# M602X.net
KiCad netlist of a schematic drawn in EAGLE
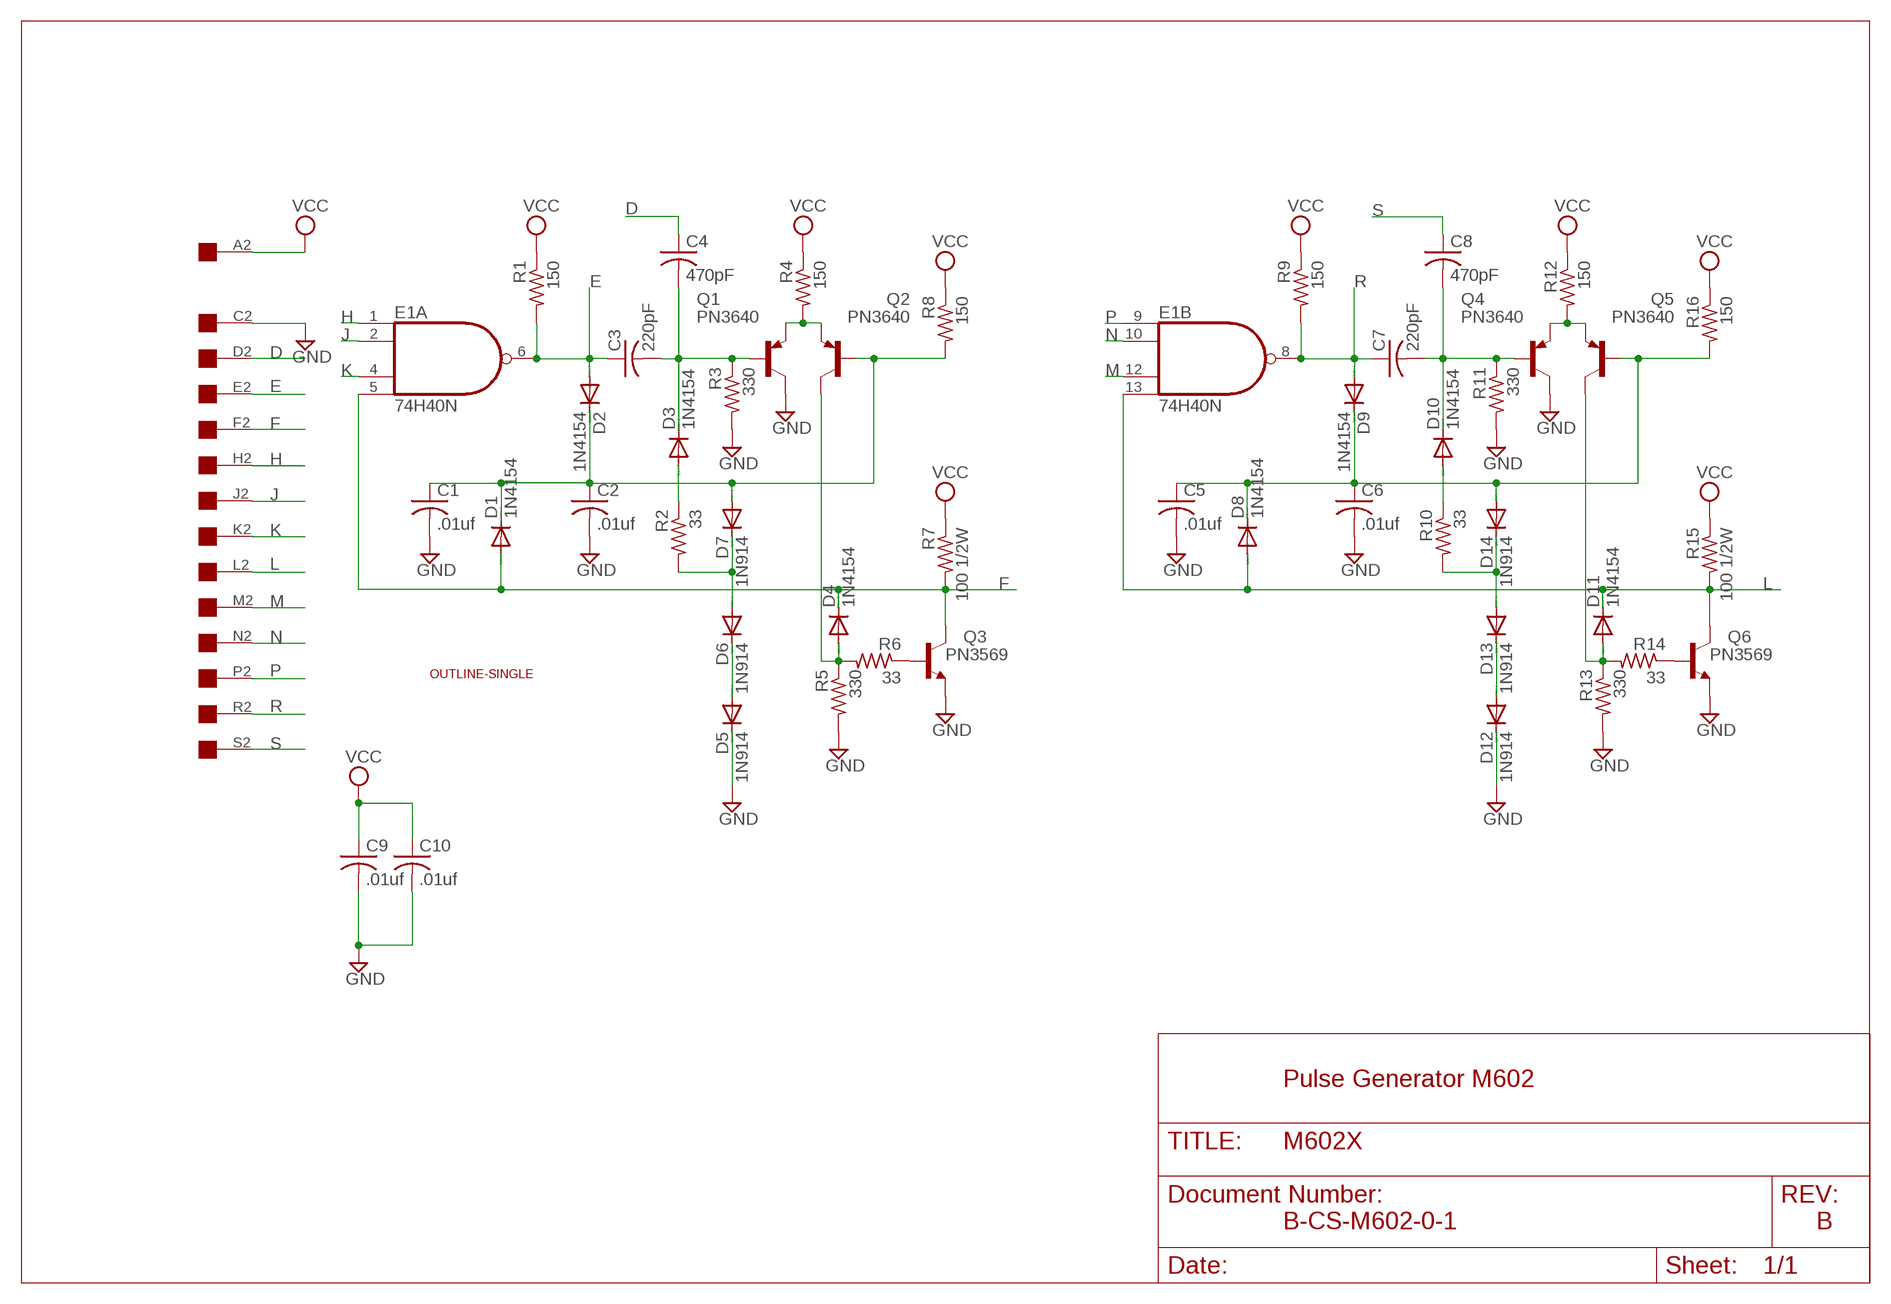
[diagram p0: schematic, sheet 1]

(export (version "E")
  (design (tool "Eeschema 10.0.6"))
  (components
    (comp (ref "C1")
      (value ".01uf")
      (footprint "eagle-import:C075-032X103")
      (libsource (lib "eagle-import") (part "C-US075-032X103"))
    )
    (comp (ref "C2")
      (value ".01uf")
      (footprint "eagle-import:C075-032X103")
      (libsource (lib "eagle-import") (part "C-US075-032X103"))
    )
    (comp (ref "C3")
      (value "220pF")
      (footprint "eagle-import:C150-054X183")
      (libsource (lib "eagle-import") (part "C-US150-054X183"))
    )
    (comp (ref "C4")
      (value "470pF")
      (footprint "eagle-import:C150-054X183")
      (libsource (lib "eagle-import") (part "C-US150-054X183"))
    )
    (comp (ref "C5")
      (value ".01uf")
      (footprint "eagle-import:C075-032X103")
      (libsource (lib "eagle-import") (part "C-US075-032X103"))
    )
    (comp (ref "C6")
      (value ".01uf")
      (footprint "eagle-import:C075-032X103")
      (libsource (lib "eagle-import") (part "C-US075-032X103"))
    )
    (comp (ref "C7")
      (value "220pF")
      (footprint "eagle-import:C150-054X183")
      (libsource (lib "eagle-import") (part "C-US150-054X183"))
    )
    (comp (ref "C8")
      (value "470pF")
      (footprint "eagle-import:C150-054X183")
      (libsource (lib "eagle-import") (part "C-US150-054X183"))
    )
    (comp (ref "C9")
      (value ".01uf")
      (footprint "eagle-import:C050-025X075")
      (libsource (lib "eagle-import") (part "C-US050-025X075"))
    )
    (comp (ref "C10")
      (value ".01uf")
      (footprint "eagle-import:C075-032X103")
      (libsource (lib "eagle-import") (part "C-US075-032X103"))
    )
    (comp (ref "D1")
      (value "1N4154")
      (footprint "eagle-import:DO41-10")
      (libsource (lib "eagle-import") (part "1N4004"))
    )
    (comp (ref "D2")
      (value "1N4154")
      (footprint "eagle-import:DO41-10")
      (libsource (lib "eagle-import") (part "1N4004"))
    )
    (comp (ref "D3")
      (value "1N4154")
      (footprint "eagle-import:DO41-10")
      (libsource (lib "eagle-import") (part "1N4004"))
    )
    (comp (ref "D4")
      (value "1N4154")
      (footprint "eagle-import:DO41-10")
      (libsource (lib "eagle-import") (part "1N4004"))
    )
    (comp (ref "D5")
      (value "1N914")
      (footprint "eagle-import:DO41-10")
      (libsource (lib "eagle-import") (part "1N4004"))
    )
    (comp (ref "D6")
      (value "1N914")
      (footprint "eagle-import:DO41-10")
      (libsource (lib "eagle-import") (part "1N4004"))
    )
    (comp (ref "D7")
      (value "1N914")
      (footprint "eagle-import:DO41-10")
      (libsource (lib "eagle-import") (part "1N4004"))
    )
    (comp (ref "D8")
      (value "1N4154")
      (footprint "eagle-import:DO41-10")
      (libsource (lib "eagle-import") (part "1N4004"))
    )
    (comp (ref "D9")
      (value "1N4154")
      (footprint "eagle-import:DO41-10")
      (libsource (lib "eagle-import") (part "1N4004"))
    )
    (comp (ref "D10")
      (value "1N4154")
      (footprint "eagle-import:DO41-10")
      (libsource (lib "eagle-import") (part "1N4004"))
    )
    (comp (ref "D11")
      (value "1N4154")
      (footprint "eagle-import:DO41-10")
      (libsource (lib "eagle-import") (part "1N4004"))
    )
    (comp (ref "D12")
      (value "1N914")
      (footprint "eagle-import:DO41-10")
      (libsource (lib "eagle-import") (part "1N4004"))
    )
    (comp (ref "D13")
      (value "1N914")
      (footprint "eagle-import:DO41-10")
      (libsource (lib "eagle-import") (part "1N4004"))
    )
    (comp (ref "D14")
      (value "1N914")
      (footprint "eagle-import:DO41-10")
      (libsource (lib "eagle-import") (part "1N4004"))
    )
    (comp (ref "E1")
      (value "74H40N")
      (footprint "eagle-import:DIL14")
      (libsource (lib "eagle-import") (part "7420NLS"))
    )
    (comp (ref "Q1")
      (value "PN3640")
      (footprint "eagle-import:TO39")
      (libsource (lib "eagle-import") (part "2N5415"))
    )
    (comp (ref "Q2")
      (value "PN3640")
      (footprint "eagle-import:TO39")
      (libsource (lib "eagle-import") (part "2N5415"))
    )
    (comp (ref "Q3")
      (value "PN3569")
      (footprint "eagle-import:TO39")
      (libsource (lib "eagle-import") (part "2N1711"))
    )
    (comp (ref "Q4")
      (value "PN3640")
      (footprint "eagle-import:TO39")
      (libsource (lib "eagle-import") (part "2N5415"))
    )
    (comp (ref "Q5")
      (value "PN3640")
      (footprint "eagle-import:TO39")
      (libsource (lib "eagle-import") (part "2N5415"))
    )
    (comp (ref "Q6")
      (value "PN3569")
      (footprint "eagle-import:TO39")
      (libsource (lib "eagle-import") (part "2N1711"))
    )
    (comp (ref "R1")
      (value "150")
      (footprint "eagle-import:0207_10")
      (libsource (lib "eagle-import") (part "R-US_0207/10"))
    )
    (comp (ref "R2")
      (value "33")
      (footprint "eagle-import:0207_10")
      (libsource (lib "eagle-import") (part "R-US_0207/10"))
    )
    (comp (ref "R3")
      (value "330")
      (footprint "eagle-import:0207_10")
      (libsource (lib "eagle-import") (part "R-US_0207/10"))
    )
    (comp (ref "R4")
      (value "150")
      (footprint "eagle-import:0207_10")
      (libsource (lib "eagle-import") (part "R-US_0207/10"))
    )
    (comp (ref "R5")
      (value "330")
      (footprint "eagle-import:0207_10")
      (libsource (lib "eagle-import") (part "R-US_0207/10"))
    )
    (comp (ref "R6")
      (value "33")
      (footprint "eagle-import:0207_10")
      (libsource (lib "eagle-import") (part "R-US_0207/10"))
    )
    (comp (ref "R7")
      (value "100 1/2W")
      (footprint "eagle-import:0309_12")
      (libsource (lib "eagle-import") (part "R-US_0309/12"))
    )
    (comp (ref "R8")
      (value "150")
      (footprint "eagle-import:0207_10")
      (libsource (lib "eagle-import") (part "R-US_0207/10"))
    )
    (comp (ref "R9")
      (value "150")
      (footprint "eagle-import:0207_10")
      (libsource (lib "eagle-import") (part "R-US_0207/10"))
    )
    (comp (ref "R10")
      (value "33")
      (footprint "eagle-import:0207_10")
      (libsource (lib "eagle-import") (part "R-US_0207/10"))
    )
    (comp (ref "R11")
      (value "330")
      (footprint "eagle-import:0207_10")
      (libsource (lib "eagle-import") (part "R-US_0207/10"))
    )
    (comp (ref "R12")
      (value "150")
      (footprint "eagle-import:0207_10")
      (libsource (lib "eagle-import") (part "R-US_0207/10"))
    )
    (comp (ref "R13")
      (value "330")
      (footprint "eagle-import:0207_10")
      (libsource (lib "eagle-import") (part "R-US_0207/10"))
    )
    (comp (ref "R14")
      (value "33")
      (footprint "eagle-import:0207_10")
      (libsource (lib "eagle-import") (part "R-US_0207/10"))
    )
    (comp (ref "R15")
      (value "100 1/2W")
      (footprint "eagle-import:0309_12")
      (libsource (lib "eagle-import") (part "R-US_0309/12"))
    )
    (comp (ref "R16")
      (value "150")
      (footprint "eagle-import:0207_10")
      (libsource (lib "eagle-import") (part "R-US_0207/10"))
    )
    (comp (ref "U$1")
      (value "EDGE-1")
      (footprint "eagle-import:EDGE-CON1")
      (libsource (lib "eagle-import") (part "EDGE-1"))
    )
    (comp (ref "U$2")
      (value "OUTLINE-SINGLE")
      (footprint "eagle-import:SINGLE")
      (libsource (lib "eagle-import") (part "OUTLINE-SINGLE"))
    )
  )
  (nets
    (net (code "1") (name "/D") (class "Default")
      (node (ref "C4") (pin "1") (pinfunction "1_1") (pintype "passive"))
      (node (ref "U$1") (pin "D2") (pinfunction "1_D2") (pintype "bidirectional"))
    )
    (net (code "2") (name "/E") (class "Default")
      (node (ref "C3") (pin "1") (pinfunction "1_1") (pintype "passive"))
      (node (ref "D2") (pin "A") (pinfunction "A_A") (pintype "passive"))
      (node (ref "E1") (pin "6") (pinfunction "O_6") (pintype "output"))
      (node (ref "R1") (pin "2") (pinfunction "2_2") (pintype "passive"))
      (node (ref "U$1") (pin "E2") (pinfunction "1_E2") (pintype "bidirectional"))
    )
    (net (code "3") (name "/F") (class "Default")
      (node (ref "D1") (pin "A") (pinfunction "A_A") (pintype "passive"))
      (node (ref "D4") (pin "C") (pinfunction "C_C") (pintype "passive"))
      (node (ref "E1") (pin "5") (pinfunction "I3_5") (pintype "input"))
      (node (ref "Q3") (pin "3") (pinfunction "C_3") (pintype "passive"))
      (node (ref "R7") (pin "2") (pinfunction "2_2") (pintype "passive"))
      (node (ref "U$1") (pin "F2") (pinfunction "1_F2") (pintype "bidirectional"))
    )
    (net (code "4") (name "/H") (class "Default")
      (node (ref "E1") (pin "1") (pinfunction "I0_1") (pintype "input"))
      (node (ref "U$1") (pin "H2") (pinfunction "1_H2") (pintype "bidirectional"))
    )
    (net (code "5") (name "/J") (class "Default")
      (node (ref "E1") (pin "2") (pinfunction "I1_2") (pintype "input"))
      (node (ref "U$1") (pin "J2") (pinfunction "1_J2") (pintype "bidirectional"))
    )
    (net (code "6") (name "/K") (class "Default")
      (node (ref "E1") (pin "4") (pinfunction "I2_4") (pintype "input"))
      (node (ref "U$1") (pin "K2") (pinfunction "1_K2") (pintype "bidirectional"))
    )
    (net (code "7") (name "/L") (class "Default")
      (node (ref "D11") (pin "C") (pinfunction "C_C") (pintype "passive"))
      (node (ref "D8") (pin "A") (pinfunction "A_A") (pintype "passive"))
      (node (ref "E1") (pin "13") (pinfunction "I3_13") (pintype "input"))
      (node (ref "Q6") (pin "3") (pinfunction "C_3") (pintype "passive"))
      (node (ref "R15") (pin "2") (pinfunction "2_2") (pintype "passive"))
      (node (ref "U$1") (pin "L2") (pinfunction "1_L2") (pintype "bidirectional"))
    )
    (net (code "8") (name "/M") (class "Default")
      (node (ref "E1") (pin "12") (pinfunction "I2_12") (pintype "input"))
      (node (ref "U$1") (pin "M2") (pinfunction "1_M2") (pintype "bidirectional"))
    )
    (net (code "9") (name "/N") (class "Default")
      (node (ref "E1") (pin "10") (pinfunction "I1_10") (pintype "input"))
      (node (ref "U$1") (pin "N2") (pinfunction "1_N2") (pintype "bidirectional"))
    )
    (net (code "10") (name "/P") (class "Default")
      (node (ref "E1") (pin "9") (pinfunction "I0_9") (pintype "input"))
      (node (ref "U$1") (pin "P2") (pinfunction "1_P2") (pintype "bidirectional"))
    )
    (net (code "11") (name "/R") (class "Default")
      (node (ref "C7") (pin "1") (pinfunction "1_1") (pintype "passive"))
      (node (ref "D9") (pin "A") (pinfunction "A_A") (pintype "passive"))
      (node (ref "E1") (pin "8") (pinfunction "O_8") (pintype "output"))
      (node (ref "R9") (pin "2") (pinfunction "2_2") (pintype "passive"))
      (node (ref "U$1") (pin "R2") (pinfunction "1_R2") (pintype "bidirectional"))
    )
    (net (code "12") (name "/S") (class "Default")
      (node (ref "C8") (pin "1") (pinfunction "1_1") (pintype "passive"))
      (node (ref "U$1") (pin "S2") (pinfunction "1_S2") (pintype "bidirectional"))
    )
    (net (code "13") (name "GND") (class "Default")
      (node (ref "C1") (pin "2") (pinfunction "2_2") (pintype "passive"))
      (node (ref "C10") (pin "2") (pinfunction "2_2") (pintype "passive"))
      (node (ref "C2") (pin "2") (pinfunction "2_2") (pintype "passive"))
      (node (ref "C5") (pin "2") (pinfunction "2_2") (pintype "passive"))
      (node (ref "C6") (pin "2") (pinfunction "2_2") (pintype "passive"))
      (node (ref "C9") (pin "2") (pinfunction "2_2") (pintype "passive"))
      (node (ref "D12") (pin "C") (pinfunction "C_C") (pintype "passive"))
      (node (ref "D5") (pin "C") (pinfunction "C_C") (pintype "passive"))
      (node (ref "Q1") (pin "3") (pinfunction "C_3") (pintype "passive"))
      (node (ref "Q3") (pin "1") (pinfunction "E_1") (pintype "passive"))
      (node (ref "Q4") (pin "3") (pinfunction "C_3") (pintype "passive"))
      (node (ref "Q6") (pin "1") (pinfunction "E_1") (pintype "passive"))
      (node (ref "R11") (pin "2") (pinfunction "2_2") (pintype "passive"))
      (node (ref "R13") (pin "2") (pinfunction "2_2") (pintype "passive"))
      (node (ref "R3") (pin "2") (pinfunction "2_2") (pintype "passive"))
      (node (ref "R5") (pin "2") (pinfunction "2_2") (pintype "passive"))
      (node (ref "U$1") (pin "C2") (pinfunction "1_C2") (pintype "bidirectional"))
    )
    (net (code "14") (name "Net-(D3-PadA)") (class "Default")
      (node (ref "D3") (pin "A") (pinfunction "A_A") (pintype "passive"))
      (node (ref "R2") (pin "1") (pinfunction "1_1") (pintype "passive"))
    )
    (net (code "15") (name "Net-(D5-PadA)") (class "Default")
      (node (ref "D5") (pin "A") (pinfunction "A_A") (pintype "passive"))
      (node (ref "D6") (pin "C") (pinfunction "C_C") (pintype "passive"))
    )
    (net (code "16") (name "Net-(D6-PadA)") (class "Default")
      (node (ref "D6") (pin "A") (pinfunction "A_A") (pintype "passive"))
      (node (ref "D7") (pin "C") (pinfunction "C_C") (pintype "passive"))
      (node (ref "R2") (pin "2") (pinfunction "2_2") (pintype "passive"))
    )
    (net (code "17") (name "Net-(D10-PadA)") (class "Default")
      (node (ref "D10") (pin "A") (pinfunction "A_A") (pintype "passive"))
      (node (ref "R10") (pin "1") (pinfunction "1_1") (pintype "passive"))
    )
    (net (code "18") (name "Net-(D12-PadA)") (class "Default")
      (node (ref "D12") (pin "A") (pinfunction "A_A") (pintype "passive"))
      (node (ref "D13") (pin "C") (pinfunction "C_C") (pintype "passive"))
    )
    (net (code "19") (name "Net-(D13-PadA)") (class "Default")
      (node (ref "D13") (pin "A") (pinfunction "A_A") (pintype "passive"))
      (node (ref "D14") (pin "C") (pinfunction "C_C") (pintype "passive"))
      (node (ref "R10") (pin "2") (pinfunction "2_2") (pintype "passive"))
    )
    (net (code "20") (name "Net-(Q1-B)") (class "Default")
      (node (ref "C3") (pin "2") (pinfunction "2_2") (pintype "passive"))
      (node (ref "C4") (pin "2") (pinfunction "2_2") (pintype "passive"))
      (node (ref "D3") (pin "C") (pinfunction "C_C") (pintype "passive"))
      (node (ref "Q1") (pin "2") (pinfunction "B_2") (pintype "passive"))
      (node (ref "R3") (pin "1") (pinfunction "1_1") (pintype "passive"))
    )
    (net (code "21") (name "Net-(Q1-E)") (class "Default")
      (node (ref "Q1") (pin "1") (pinfunction "E_1") (pintype "passive"))
      (node (ref "Q2") (pin "1") (pinfunction "E_1") (pintype "passive"))
      (node (ref "R4") (pin "2") (pinfunction "2_2") (pintype "passive"))
    )
    (net (code "22") (name "Net-(Q2-B)") (class "Default")
      (node (ref "C1") (pin "1") (pinfunction "1_1") (pintype "passive"))
      (node (ref "C2") (pin "1") (pinfunction "1_1") (pintype "passive"))
      (node (ref "D1") (pin "C") (pinfunction "C_C") (pintype "passive"))
      (node (ref "D2") (pin "C") (pinfunction "C_C") (pintype "passive"))
      (node (ref "D7") (pin "A") (pinfunction "A_A") (pintype "passive"))
      (node (ref "Q2") (pin "2") (pinfunction "B_2") (pintype "passive"))
      (node (ref "R8") (pin "2") (pinfunction "2_2") (pintype "passive"))
    )
    (net (code "23") (name "Net-(Q2-C)") (class "Default")
      (node (ref "D4") (pin "A") (pinfunction "A_A") (pintype "passive"))
      (node (ref "Q2") (pin "3") (pinfunction "C_3") (pintype "passive"))
      (node (ref "R5") (pin "1") (pinfunction "1_1") (pintype "passive"))
      (node (ref "R6") (pin "2") (pinfunction "2_2") (pintype "passive"))
    )
    (net (code "24") (name "Net-(Q3-B)") (class "Default")
      (node (ref "Q3") (pin "2") (pinfunction "B_2") (pintype "passive"))
      (node (ref "R6") (pin "1") (pinfunction "1_1") (pintype "passive"))
    )
    (net (code "25") (name "Net-(Q4-B)") (class "Default")
      (node (ref "C7") (pin "2") (pinfunction "2_2") (pintype "passive"))
      (node (ref "C8") (pin "2") (pinfunction "2_2") (pintype "passive"))
      (node (ref "D10") (pin "C") (pinfunction "C_C") (pintype "passive"))
      (node (ref "Q4") (pin "2") (pinfunction "B_2") (pintype "passive"))
      (node (ref "R11") (pin "1") (pinfunction "1_1") (pintype "passive"))
    )
    (net (code "26") (name "Net-(Q4-E)") (class "Default")
      (node (ref "Q4") (pin "1") (pinfunction "E_1") (pintype "passive"))
      (node (ref "Q5") (pin "1") (pinfunction "E_1") (pintype "passive"))
      (node (ref "R12") (pin "2") (pinfunction "2_2") (pintype "passive"))
    )
    (net (code "27") (name "Net-(Q5-B)") (class "Default")
      (node (ref "C5") (pin "1") (pinfunction "1_1") (pintype "passive"))
      (node (ref "C6") (pin "1") (pinfunction "1_1") (pintype "passive"))
      (node (ref "D14") (pin "A") (pinfunction "A_A") (pintype "passive"))
      (node (ref "D8") (pin "C") (pinfunction "C_C") (pintype "passive"))
      (node (ref "D9") (pin "C") (pinfunction "C_C") (pintype "passive"))
      (node (ref "Q5") (pin "2") (pinfunction "B_2") (pintype "passive"))
      (node (ref "R16") (pin "2") (pinfunction "2_2") (pintype "passive"))
    )
    (net (code "28") (name "Net-(Q5-C)") (class "Default")
      (node (ref "D11") (pin "A") (pinfunction "A_A") (pintype "passive"))
      (node (ref "Q5") (pin "3") (pinfunction "C_3") (pintype "passive"))
      (node (ref "R13") (pin "1") (pinfunction "1_1") (pintype "passive"))
      (node (ref "R14") (pin "2") (pinfunction "2_2") (pintype "passive"))
    )
    (net (code "29") (name "Net-(Q6-B)") (class "Default")
      (node (ref "Q6") (pin "2") (pinfunction "B_2") (pintype "passive"))
      (node (ref "R14") (pin "1") (pinfunction "1_1") (pintype "passive"))
    )
    (net (code "30") (name "VCC") (class "Default")
      (node (ref "C10") (pin "1") (pinfunction "1_1") (pintype "passive"))
      (node (ref "C9") (pin "1") (pinfunction "1_1") (pintype "passive"))
      (node (ref "R1") (pin "1") (pinfunction "1_1") (pintype "passive"))
      (node (ref "R12") (pin "1") (pinfunction "1_1") (pintype "passive"))
      (node (ref "R15") (pin "1") (pinfunction "1_1") (pintype "passive"))
      (node (ref "R16") (pin "1") (pinfunction "1_1") (pintype "passive"))
      (node (ref "R4") (pin "1") (pinfunction "1_1") (pintype "passive"))
      (node (ref "R7") (pin "1") (pinfunction "1_1") (pintype "passive"))
      (node (ref "R8") (pin "1") (pinfunction "1_1") (pintype "passive"))
      (node (ref "R9") (pin "1") (pinfunction "1_1") (pintype "passive"))
      (node (ref "U$1") (pin "A2") (pinfunction "1_A2") (pintype "bidirectional"))
    )
  )
)
